# MyoWare_Proto_Shield.net
KiCad netlist of a schematic drawn in EAGLE
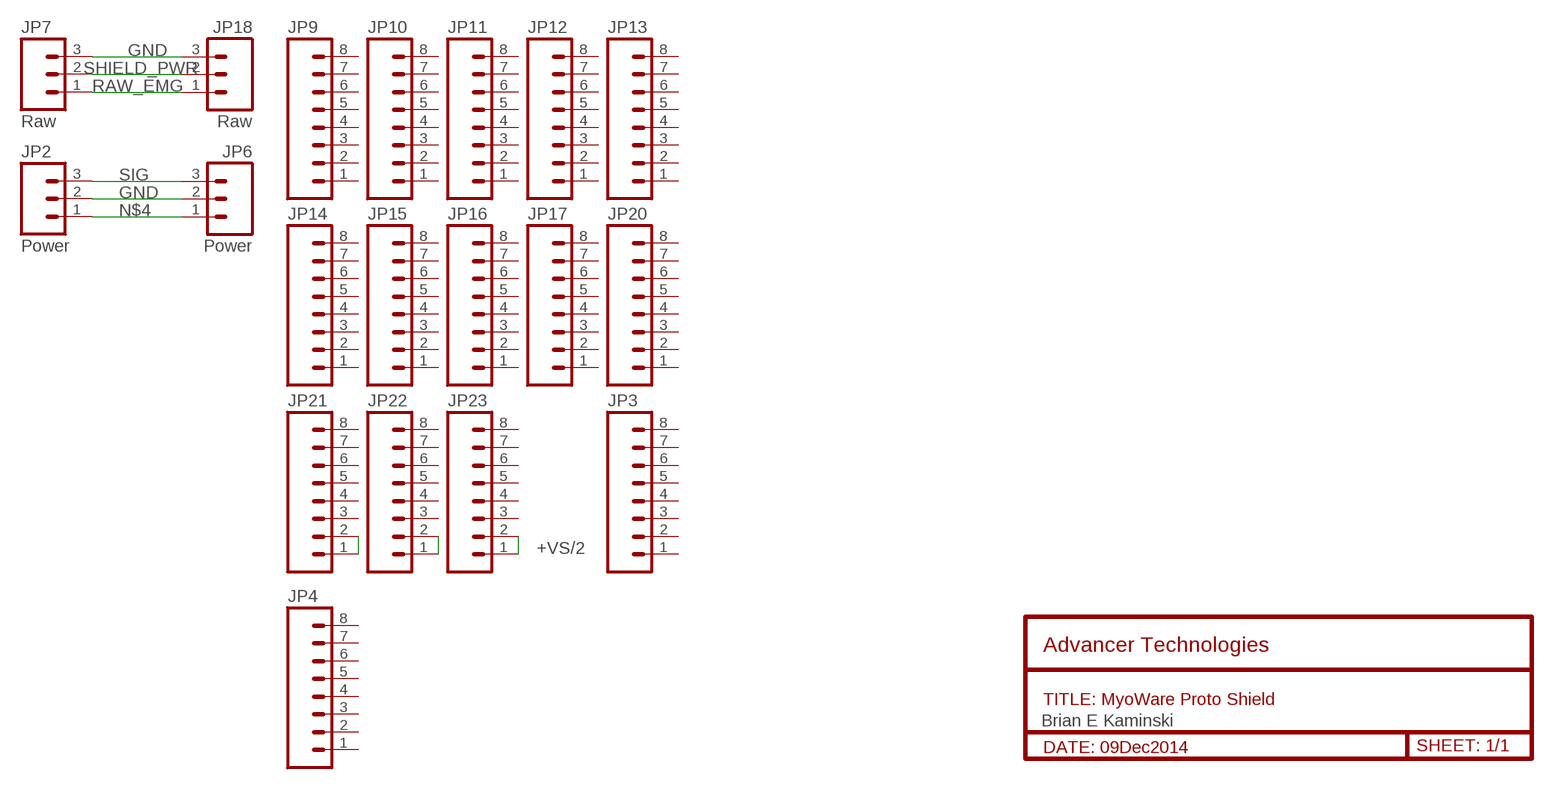
[diagram p0: schematic, sheet 1]

(export (version "E")
  (design (tool "Eeschema 10.0.6"))
  (components
    (comp (ref "JP2")
      (value "Power")
      (footprint "eagle-import:1X03_NO_SILK")
      (libsource (lib "eagle-import") (part "M031X03_NO_SILK"))
    )
    (comp (ref "JP3")
      (value "M08NO_SILK")
      (footprint "eagle-import:1X08_NO_SILK")
      (libsource (lib "eagle-import") (part "M08NO_SILK"))
    )
    (comp (ref "JP4")
      (value "M08NO_SILK")
      (footprint "eagle-import:1X08_NO_SILK")
      (libsource (lib "eagle-import") (part "M08NO_SILK"))
    )
    (comp (ref "JP6")
      (value "Power")
      (footprint "eagle-import:1X03_NO_SILK")
      (libsource (lib "eagle-import") (part "M031X03_NO_SILK"))
    )
    (comp (ref "JP7")
      (value "Raw")
      (footprint "eagle-import:1X03_NO_SILK")
      (libsource (lib "eagle-import") (part "M031X03_NO_SILK"))
    )
    (comp (ref "JP9")
      (value "M08NO_SILK")
      (footprint "eagle-import:1X08_NO_SILK")
      (libsource (lib "eagle-import") (part "M08NO_SILK"))
    )
    (comp (ref "JP10")
      (value "M08NO_SILK")
      (footprint "eagle-import:1X08_NO_SILK")
      (libsource (lib "eagle-import") (part "M08NO_SILK"))
    )
    (comp (ref "JP11")
      (value "M08NO_SILK")
      (footprint "eagle-import:1X08_NO_SILK")
      (libsource (lib "eagle-import") (part "M08NO_SILK"))
    )
    (comp (ref "JP12")
      (value "M08NO_SILK")
      (footprint "eagle-import:1X08_NO_SILK")
      (libsource (lib "eagle-import") (part "M08NO_SILK"))
    )
    (comp (ref "JP13")
      (value "M08NO_SILK")
      (footprint "eagle-import:1X08_NO_SILK")
      (libsource (lib "eagle-import") (part "M08NO_SILK"))
    )
    (comp (ref "JP14")
      (value "M08NO_SILK")
      (footprint "eagle-import:1X08_NO_SILK")
      (libsource (lib "eagle-import") (part "M08NO_SILK"))
    )
    (comp (ref "JP15")
      (value "M08NO_SILK")
      (footprint "eagle-import:1X08_NO_SILK")
      (libsource (lib "eagle-import") (part "M08NO_SILK"))
    )
    (comp (ref "JP16")
      (value "M08NO_SILK")
      (footprint "eagle-import:1X08_NO_SILK")
      (libsource (lib "eagle-import") (part "M08NO_SILK"))
    )
    (comp (ref "JP17")
      (value "M08NO_SILK")
      (footprint "eagle-import:1X08_NO_SILK")
      (libsource (lib "eagle-import") (part "M08NO_SILK"))
    )
    (comp (ref "JP18")
      (value "Raw")
      (footprint "eagle-import:1X03_NO_SILK")
      (libsource (lib "eagle-import") (part "M031X03_NO_SILK"))
    )
    (comp (ref "JP20")
      (value "M08NO_SILK")
      (footprint "eagle-import:1X08_NO_SILK")
      (libsource (lib "eagle-import") (part "M08NO_SILK"))
    )
    (comp (ref "JP21")
      (value "M08NO_SILK")
      (footprint "eagle-import:1X08_NO_SILK")
      (libsource (lib "eagle-import") (part "M08NO_SILK"))
    )
    (comp (ref "JP22")
      (value "M08NO_SILK")
      (footprint "eagle-import:1X08_NO_SILK")
      (libsource (lib "eagle-import") (part "M08NO_SILK"))
    )
    (comp (ref "JP23")
      (value "M08NO_SILK")
      (footprint "eagle-import:1X08_NO_SILK")
      (libsource (lib "eagle-import") (part "M08NO_SILK"))
    )
  )
  (nets
    (net (code "1") (name "/+VS{slash}2") (class "Default")
      (node (ref "JP23") (pin "1") (pinfunction "1_1") (pintype "passive"))
      (node (ref "JP23") (pin "2") (pinfunction "2_2") (pintype "passive"))
    )
    (net (code "2") (name "/GND") (class "Default")
      (node (ref "JP18") (pin "3") (pinfunction "3_3") (pintype "passive"))
      (node (ref "JP2") (pin "2") (pinfunction "2_2") (pintype "passive"))
      (node (ref "JP6") (pin "2") (pinfunction "2_2") (pintype "passive"))
      (node (ref "JP7") (pin "3") (pinfunction "3_3") (pintype "passive"))
    )
    (net (code "3") (name "/N$4") (class "Default")
      (node (ref "JP2") (pin "1") (pinfunction "1_1") (pintype "passive"))
      (node (ref "JP6") (pin "1") (pinfunction "1_1") (pintype "passive"))
    )
    (net (code "4") (name "/RAW_EMG") (class "Default")
      (node (ref "JP18") (pin "1") (pinfunction "1_1") (pintype "passive"))
      (node (ref "JP7") (pin "1") (pinfunction "1_1") (pintype "passive"))
    )
    (net (code "5") (name "/SHIELD_PWR") (class "Default")
      (node (ref "JP18") (pin "2") (pinfunction "2_2") (pintype "passive"))
      (node (ref "JP7") (pin "2") (pinfunction "2_2") (pintype "passive"))
    )
    (net (code "6") (name "/SIG") (class "Default")
      (node (ref "JP2") (pin "3") (pinfunction "3_3") (pintype "passive"))
      (node (ref "JP6") (pin "3") (pinfunction "3_3") (pintype "passive"))
    )
    (net (code "7") (name "Net-(JP21-Pad1)") (class "Default")
      (node (ref "JP21") (pin "1") (pinfunction "1_1") (pintype "passive"))
      (node (ref "JP21") (pin "2") (pinfunction "2_2") (pintype "passive"))
    )
    (net (code "8") (name "Net-(JP22-Pad1)") (class "Default")
      (node (ref "JP22") (pin "1") (pinfunction "1_1") (pintype "passive"))
      (node (ref "JP22") (pin "2") (pinfunction "2_2") (pintype "passive"))
    )
    (net (code "9") (name "unconnected-(JP3-Pad1)") (class "Default")
      (node (ref "JP3") (pin "1") (pinfunction "1_1") (pintype "passive"))
    )
    (net (code "10") (name "unconnected-(JP3-Pad2)") (class "Default")
      (node (ref "JP3") (pin "2") (pinfunction "2_2") (pintype "passive"))
    )
    (net (code "11") (name "unconnected-(JP3-Pad3)") (class "Default")
      (node (ref "JP3") (pin "3") (pinfunction "3_3") (pintype "passive"))
    )
    (net (code "12") (name "unconnected-(JP3-Pad4)") (class "Default")
      (node (ref "JP3") (pin "4") (pinfunction "4_4") (pintype "passive"))
    )
    (net (code "13") (name "unconnected-(JP3-Pad5)") (class "Default")
      (node (ref "JP3") (pin "5") (pinfunction "5_5") (pintype "passive"))
    )
    (net (code "14") (name "unconnected-(JP3-Pad6)") (class "Default")
      (node (ref "JP3") (pin "6") (pinfunction "6_6") (pintype "passive"))
    )
    (net (code "15") (name "unconnected-(JP3-Pad7)") (class "Default")
      (node (ref "JP3") (pin "7") (pinfunction "7_7") (pintype "passive"))
    )
    (net (code "16") (name "unconnected-(JP3-Pad8)") (class "Default")
      (node (ref "JP3") (pin "8") (pinfunction "8_8") (pintype "passive"))
    )
    (net (code "17") (name "unconnected-(JP4-Pad1)") (class "Default")
      (node (ref "JP4") (pin "1") (pinfunction "1_1") (pintype "passive"))
    )
    (net (code "18") (name "unconnected-(JP4-Pad2)") (class "Default")
      (node (ref "JP4") (pin "2") (pinfunction "2_2") (pintype "passive"))
    )
    (net (code "19") (name "unconnected-(JP4-Pad3)") (class "Default")
      (node (ref "JP4") (pin "3") (pinfunction "3_3") (pintype "passive"))
    )
    (net (code "20") (name "unconnected-(JP4-Pad4)") (class "Default")
      (node (ref "JP4") (pin "4") (pinfunction "4_4") (pintype "passive"))
    )
    (net (code "21") (name "unconnected-(JP4-Pad5)") (class "Default")
      (node (ref "JP4") (pin "5") (pinfunction "5_5") (pintype "passive"))
    )
    (net (code "22") (name "unconnected-(JP4-Pad6)") (class "Default")
      (node (ref "JP4") (pin "6") (pinfunction "6_6") (pintype "passive"))
    )
    (net (code "23") (name "unconnected-(JP4-Pad7)") (class "Default")
      (node (ref "JP4") (pin "7") (pinfunction "7_7") (pintype "passive"))
    )
    (net (code "24") (name "unconnected-(JP4-Pad8)") (class "Default")
      (node (ref "JP4") (pin "8") (pinfunction "8_8") (pintype "passive"))
    )
    (net (code "25") (name "unconnected-(JP9-Pad1)") (class "Default")
      (node (ref "JP9") (pin "1") (pinfunction "1_1") (pintype "passive"))
    )
    (net (code "26") (name "unconnected-(JP9-Pad2)") (class "Default")
      (node (ref "JP9") (pin "2") (pinfunction "2_2") (pintype "passive"))
    )
    (net (code "27") (name "unconnected-(JP9-Pad3)") (class "Default")
      (node (ref "JP9") (pin "3") (pinfunction "3_3") (pintype "passive"))
    )
    (net (code "28") (name "unconnected-(JP9-Pad4)") (class "Default")
      (node (ref "JP9") (pin "4") (pinfunction "4_4") (pintype "passive"))
    )
    (net (code "29") (name "unconnected-(JP9-Pad5)") (class "Default")
      (node (ref "JP9") (pin "5") (pinfunction "5_5") (pintype "passive"))
    )
    (net (code "30") (name "unconnected-(JP9-Pad6)") (class "Default")
      (node (ref "JP9") (pin "6") (pinfunction "6_6") (pintype "passive"))
    )
    (net (code "31") (name "unconnected-(JP9-Pad7)") (class "Default")
      (node (ref "JP9") (pin "7") (pinfunction "7_7") (pintype "passive"))
    )
    (net (code "32") (name "unconnected-(JP9-Pad8)") (class "Default")
      (node (ref "JP9") (pin "8") (pinfunction "8_8") (pintype "passive"))
    )
    (net (code "33") (name "unconnected-(JP10-Pad1)") (class "Default")
      (node (ref "JP10") (pin "1") (pinfunction "1_1") (pintype "passive"))
    )
    (net (code "34") (name "unconnected-(JP10-Pad2)") (class "Default")
      (node (ref "JP10") (pin "2") (pinfunction "2_2") (pintype "passive"))
    )
    (net (code "35") (name "unconnected-(JP10-Pad3)") (class "Default")
      (node (ref "JP10") (pin "3") (pinfunction "3_3") (pintype "passive"))
    )
    (net (code "36") (name "unconnected-(JP10-Pad4)") (class "Default")
      (node (ref "JP10") (pin "4") (pinfunction "4_4") (pintype "passive"))
    )
    (net (code "37") (name "unconnected-(JP10-Pad5)") (class "Default")
      (node (ref "JP10") (pin "5") (pinfunction "5_5") (pintype "passive"))
    )
    (net (code "38") (name "unconnected-(JP10-Pad6)") (class "Default")
      (node (ref "JP10") (pin "6") (pinfunction "6_6") (pintype "passive"))
    )
    (net (code "39") (name "unconnected-(JP10-Pad7)") (class "Default")
      (node (ref "JP10") (pin "7") (pinfunction "7_7") (pintype "passive"))
    )
    (net (code "40") (name "unconnected-(JP10-Pad8)") (class "Default")
      (node (ref "JP10") (pin "8") (pinfunction "8_8") (pintype "passive"))
    )
    (net (code "41") (name "unconnected-(JP11-Pad1)") (class "Default")
      (node (ref "JP11") (pin "1") (pinfunction "1_1") (pintype "passive"))
    )
    (net (code "42") (name "unconnected-(JP11-Pad2)") (class "Default")
      (node (ref "JP11") (pin "2") (pinfunction "2_2") (pintype "passive"))
    )
    (net (code "43") (name "unconnected-(JP11-Pad3)") (class "Default")
      (node (ref "JP11") (pin "3") (pinfunction "3_3") (pintype "passive"))
    )
    (net (code "44") (name "unconnected-(JP11-Pad4)") (class "Default")
      (node (ref "JP11") (pin "4") (pinfunction "4_4") (pintype "passive"))
    )
    (net (code "45") (name "unconnected-(JP11-Pad5)") (class "Default")
      (node (ref "JP11") (pin "5") (pinfunction "5_5") (pintype "passive"))
    )
    (net (code "46") (name "unconnected-(JP11-Pad6)") (class "Default")
      (node (ref "JP11") (pin "6") (pinfunction "6_6") (pintype "passive"))
    )
    (net (code "47") (name "unconnected-(JP11-Pad7)") (class "Default")
      (node (ref "JP11") (pin "7") (pinfunction "7_7") (pintype "passive"))
    )
    (net (code "48") (name "unconnected-(JP11-Pad8)") (class "Default")
      (node (ref "JP11") (pin "8") (pinfunction "8_8") (pintype "passive"))
    )
    (net (code "49") (name "unconnected-(JP12-Pad1)") (class "Default")
      (node (ref "JP12") (pin "1") (pinfunction "1_1") (pintype "passive"))
    )
    (net (code "50") (name "unconnected-(JP12-Pad2)") (class "Default")
      (node (ref "JP12") (pin "2") (pinfunction "2_2") (pintype "passive"))
    )
    (net (code "51") (name "unconnected-(JP12-Pad3)") (class "Default")
      (node (ref "JP12") (pin "3") (pinfunction "3_3") (pintype "passive"))
    )
    (net (code "52") (name "unconnected-(JP12-Pad4)") (class "Default")
      (node (ref "JP12") (pin "4") (pinfunction "4_4") (pintype "passive"))
    )
    (net (code "53") (name "unconnected-(JP12-Pad5)") (class "Default")
      (node (ref "JP12") (pin "5") (pinfunction "5_5") (pintype "passive"))
    )
    (net (code "54") (name "unconnected-(JP12-Pad6)") (class "Default")
      (node (ref "JP12") (pin "6") (pinfunction "6_6") (pintype "passive"))
    )
    (net (code "55") (name "unconnected-(JP12-Pad7)") (class "Default")
      (node (ref "JP12") (pin "7") (pinfunction "7_7") (pintype "passive"))
    )
    (net (code "56") (name "unconnected-(JP12-Pad8)") (class "Default")
      (node (ref "JP12") (pin "8") (pinfunction "8_8") (pintype "passive"))
    )
    (net (code "57") (name "unconnected-(JP13-Pad1)") (class "Default")
      (node (ref "JP13") (pin "1") (pinfunction "1_1") (pintype "passive"))
    )
    (net (code "58") (name "unconnected-(JP13-Pad2)") (class "Default")
      (node (ref "JP13") (pin "2") (pinfunction "2_2") (pintype "passive"))
    )
    (net (code "59") (name "unconnected-(JP13-Pad3)") (class "Default")
      (node (ref "JP13") (pin "3") (pinfunction "3_3") (pintype "passive"))
    )
    (net (code "60") (name "unconnected-(JP13-Pad4)") (class "Default")
      (node (ref "JP13") (pin "4") (pinfunction "4_4") (pintype "passive"))
    )
    (net (code "61") (name "unconnected-(JP13-Pad5)") (class "Default")
      (node (ref "JP13") (pin "5") (pinfunction "5_5") (pintype "passive"))
    )
    (net (code "62") (name "unconnected-(JP13-Pad6)") (class "Default")
      (node (ref "JP13") (pin "6") (pinfunction "6_6") (pintype "passive"))
    )
    (net (code "63") (name "unconnected-(JP13-Pad7)") (class "Default")
      (node (ref "JP13") (pin "7") (pinfunction "7_7") (pintype "passive"))
    )
    (net (code "64") (name "unconnected-(JP13-Pad8)") (class "Default")
      (node (ref "JP13") (pin "8") (pinfunction "8_8") (pintype "passive"))
    )
    (net (code "65") (name "unconnected-(JP14-Pad1)") (class "Default")
      (node (ref "JP14") (pin "1") (pinfunction "1_1") (pintype "passive"))
    )
    (net (code "66") (name "unconnected-(JP14-Pad2)") (class "Default")
      (node (ref "JP14") (pin "2") (pinfunction "2_2") (pintype "passive"))
    )
    (net (code "67") (name "unconnected-(JP14-Pad3)") (class "Default")
      (node (ref "JP14") (pin "3") (pinfunction "3_3") (pintype "passive"))
    )
    (net (code "68") (name "unconnected-(JP14-Pad4)") (class "Default")
      (node (ref "JP14") (pin "4") (pinfunction "4_4") (pintype "passive"))
    )
    (net (code "69") (name "unconnected-(JP14-Pad5)") (class "Default")
      (node (ref "JP14") (pin "5") (pinfunction "5_5") (pintype "passive"))
    )
    (net (code "70") (name "unconnected-(JP14-Pad6)") (class "Default")
      (node (ref "JP14") (pin "6") (pinfunction "6_6") (pintype "passive"))
    )
    (net (code "71") (name "unconnected-(JP14-Pad7)") (class "Default")
      (node (ref "JP14") (pin "7") (pinfunction "7_7") (pintype "passive"))
    )
    (net (code "72") (name "unconnected-(JP14-Pad8)") (class "Default")
      (node (ref "JP14") (pin "8") (pinfunction "8_8") (pintype "passive"))
    )
    (net (code "73") (name "unconnected-(JP15-Pad1)") (class "Default")
      (node (ref "JP15") (pin "1") (pinfunction "1_1") (pintype "passive"))
    )
    (net (code "74") (name "unconnected-(JP15-Pad2)") (class "Default")
      (node (ref "JP15") (pin "2") (pinfunction "2_2") (pintype "passive"))
    )
    (net (code "75") (name "unconnected-(JP15-Pad3)") (class "Default")
      (node (ref "JP15") (pin "3") (pinfunction "3_3") (pintype "passive"))
    )
    (net (code "76") (name "unconnected-(JP15-Pad4)") (class "Default")
      (node (ref "JP15") (pin "4") (pinfunction "4_4") (pintype "passive"))
    )
    (net (code "77") (name "unconnected-(JP15-Pad5)") (class "Default")
      (node (ref "JP15") (pin "5") (pinfunction "5_5") (pintype "passive"))
    )
    (net (code "78") (name "unconnected-(JP15-Pad6)") (class "Default")
      (node (ref "JP15") (pin "6") (pinfunction "6_6") (pintype "passive"))
    )
    (net (code "79") (name "unconnected-(JP15-Pad7)") (class "Default")
      (node (ref "JP15") (pin "7") (pinfunction "7_7") (pintype "passive"))
    )
    (net (code "80") (name "unconnected-(JP15-Pad8)") (class "Default")
      (node (ref "JP15") (pin "8") (pinfunction "8_8") (pintype "passive"))
    )
    (net (code "81") (name "unconnected-(JP16-Pad1)") (class "Default")
      (node (ref "JP16") (pin "1") (pinfunction "1_1") (pintype "passive"))
    )
    (net (code "82") (name "unconnected-(JP16-Pad2)") (class "Default")
      (node (ref "JP16") (pin "2") (pinfunction "2_2") (pintype "passive"))
    )
    (net (code "83") (name "unconnected-(JP16-Pad3)") (class "Default")
      (node (ref "JP16") (pin "3") (pinfunction "3_3") (pintype "passive"))
    )
    (net (code "84") (name "unconnected-(JP16-Pad4)") (class "Default")
      (node (ref "JP16") (pin "4") (pinfunction "4_4") (pintype "passive"))
    )
    (net (code "85") (name "unconnected-(JP16-Pad5)") (class "Default")
      (node (ref "JP16") (pin "5") (pinfunction "5_5") (pintype "passive"))
    )
    (net (code "86") (name "unconnected-(JP16-Pad6)") (class "Default")
      (node (ref "JP16") (pin "6") (pinfunction "6_6") (pintype "passive"))
    )
    (net (code "87") (name "unconnected-(JP16-Pad7)") (class "Default")
      (node (ref "JP16") (pin "7") (pinfunction "7_7") (pintype "passive"))
    )
    (net (code "88") (name "unconnected-(JP16-Pad8)") (class "Default")
      (node (ref "JP16") (pin "8") (pinfunction "8_8") (pintype "passive"))
    )
    (net (code "89") (name "unconnected-(JP17-Pad1)") (class "Default")
      (node (ref "JP17") (pin "1") (pinfunction "1_1") (pintype "passive"))
    )
    (net (code "90") (name "unconnected-(JP17-Pad2)") (class "Default")
      (node (ref "JP17") (pin "2") (pinfunction "2_2") (pintype "passive"))
    )
    (net (code "91") (name "unconnected-(JP17-Pad3)") (class "Default")
      (node (ref "JP17") (pin "3") (pinfunction "3_3") (pintype "passive"))
    )
    (net (code "92") (name "unconnected-(JP17-Pad4)") (class "Default")
      (node (ref "JP17") (pin "4") (pinfunction "4_4") (pintype "passive"))
    )
    (net (code "93") (name "unconnected-(JP17-Pad5)") (class "Default")
      (node (ref "JP17") (pin "5") (pinfunction "5_5") (pintype "passive"))
    )
    (net (code "94") (name "unconnected-(JP17-Pad6)") (class "Default")
      (node (ref "JP17") (pin "6") (pinfunction "6_6") (pintype "passive"))
    )
    (net (code "95") (name "unconnected-(JP17-Pad7)") (class "Default")
      (node (ref "JP17") (pin "7") (pinfunction "7_7") (pintype "passive"))
    )
    (net (code "96") (name "unconnected-(JP17-Pad8)") (class "Default")
      (node (ref "JP17") (pin "8") (pinfunction "8_8") (pintype "passive"))
    )
    (net (code "97") (name "unconnected-(JP20-Pad1)") (class "Default")
      (node (ref "JP20") (pin "1") (pinfunction "1_1") (pintype "passive"))
    )
    (net (code "98") (name "unconnected-(JP20-Pad2)") (class "Default")
      (node (ref "JP20") (pin "2") (pinfunction "2_2") (pintype "passive"))
    )
    (net (code "99") (name "unconnected-(JP20-Pad3)") (class "Default")
      (node (ref "JP20") (pin "3") (pinfunction "3_3") (pintype "passive"))
    )
    (net (code "100") (name "unconnected-(JP20-Pad4)") (class "Default")
      (node (ref "JP20") (pin "4") (pinfunction "4_4") (pintype "passive"))
    )
    (net (code "101") (name "unconnected-(JP20-Pad5)") (class "Default")
      (node (ref "JP20") (pin "5") (pinfunction "5_5") (pintype "passive"))
    )
    (net (code "102") (name "unconnected-(JP20-Pad6)") (class "Default")
      (node (ref "JP20") (pin "6") (pinfunction "6_6") (pintype "passive"))
    )
    (net (code "103") (name "unconnected-(JP20-Pad7)") (class "Default")
      (node (ref "JP20") (pin "7") (pinfunction "7_7") (pintype "passive"))
    )
    (net (code "104") (name "unconnected-(JP20-Pad8)") (class "Default")
      (node (ref "JP20") (pin "8") (pinfunction "8_8") (pintype "passive"))
    )
    (net (code "105") (name "unconnected-(JP21-Pad3)") (class "Default")
      (node (ref "JP21") (pin "3") (pinfunction "3_3") (pintype "passive"))
    )
    (net (code "106") (name "unconnected-(JP21-Pad4)") (class "Default")
      (node (ref "JP21") (pin "4") (pinfunction "4_4") (pintype "passive"))
    )
    (net (code "107") (name "unconnected-(JP21-Pad5)") (class "Default")
      (node (ref "JP21") (pin "5") (pinfunction "5_5") (pintype "passive"))
    )
    (net (code "108") (name "unconnected-(JP21-Pad6)") (class "Default")
      (node (ref "JP21") (pin "6") (pinfunction "6_6") (pintype "passive"))
    )
    (net (code "109") (name "unconnected-(JP21-Pad7)") (class "Default")
      (node (ref "JP21") (pin "7") (pinfunction "7_7") (pintype "passive"))
    )
    (net (code "110") (name "unconnected-(JP21-Pad8)") (class "Default")
      (node (ref "JP21") (pin "8") (pinfunction "8_8") (pintype "passive"))
    )
    (net (code "111") (name "unconnected-(JP22-Pad3)") (class "Default")
      (node (ref "JP22") (pin "3") (pinfunction "3_3") (pintype "passive"))
    )
    (net (code "112") (name "unconnected-(JP22-Pad4)") (class "Default")
      (node (ref "JP22") (pin "4") (pinfunction "4_4") (pintype "passive"))
    )
    (net (code "113") (name "unconnected-(JP22-Pad5)") (class "Default")
      (node (ref "JP22") (pin "5") (pinfunction "5_5") (pintype "passive"))
    )
    (net (code "114") (name "unconnected-(JP22-Pad6)") (class "Default")
      (node (ref "JP22") (pin "6") (pinfunction "6_6") (pintype "passive"))
    )
    (net (code "115") (name "unconnected-(JP22-Pad7)") (class "Default")
      (node (ref "JP22") (pin "7") (pinfunction "7_7") (pintype "passive"))
    )
    (net (code "116") (name "unconnected-(JP22-Pad8)") (class "Default")
      (node (ref "JP22") (pin "8") (pinfunction "8_8") (pintype "passive"))
    )
    (net (code "117") (name "unconnected-(JP23-Pad3)") (class "Default")
      (node (ref "JP23") (pin "3") (pinfunction "3_3") (pintype "passive"))
    )
    (net (code "118") (name "unconnected-(JP23-Pad4)") (class "Default")
      (node (ref "JP23") (pin "4") (pinfunction "4_4") (pintype "passive"))
    )
    (net (code "119") (name "unconnected-(JP23-Pad5)") (class "Default")
      (node (ref "JP23") (pin "5") (pinfunction "5_5") (pintype "passive"))
    )
    (net (code "120") (name "unconnected-(JP23-Pad6)") (class "Default")
      (node (ref "JP23") (pin "6") (pinfunction "6_6") (pintype "passive"))
    )
    (net (code "121") (name "unconnected-(JP23-Pad7)") (class "Default")
      (node (ref "JP23") (pin "7") (pinfunction "7_7") (pintype "passive"))
    )
    (net (code "122") (name "unconnected-(JP23-Pad8)") (class "Default")
      (node (ref "JP23") (pin "8") (pinfunction "8_8") (pintype "passive"))
    )
  )
)
